# hydrop_board.net
KiCad netlist of a schematic drawn in EAGLE
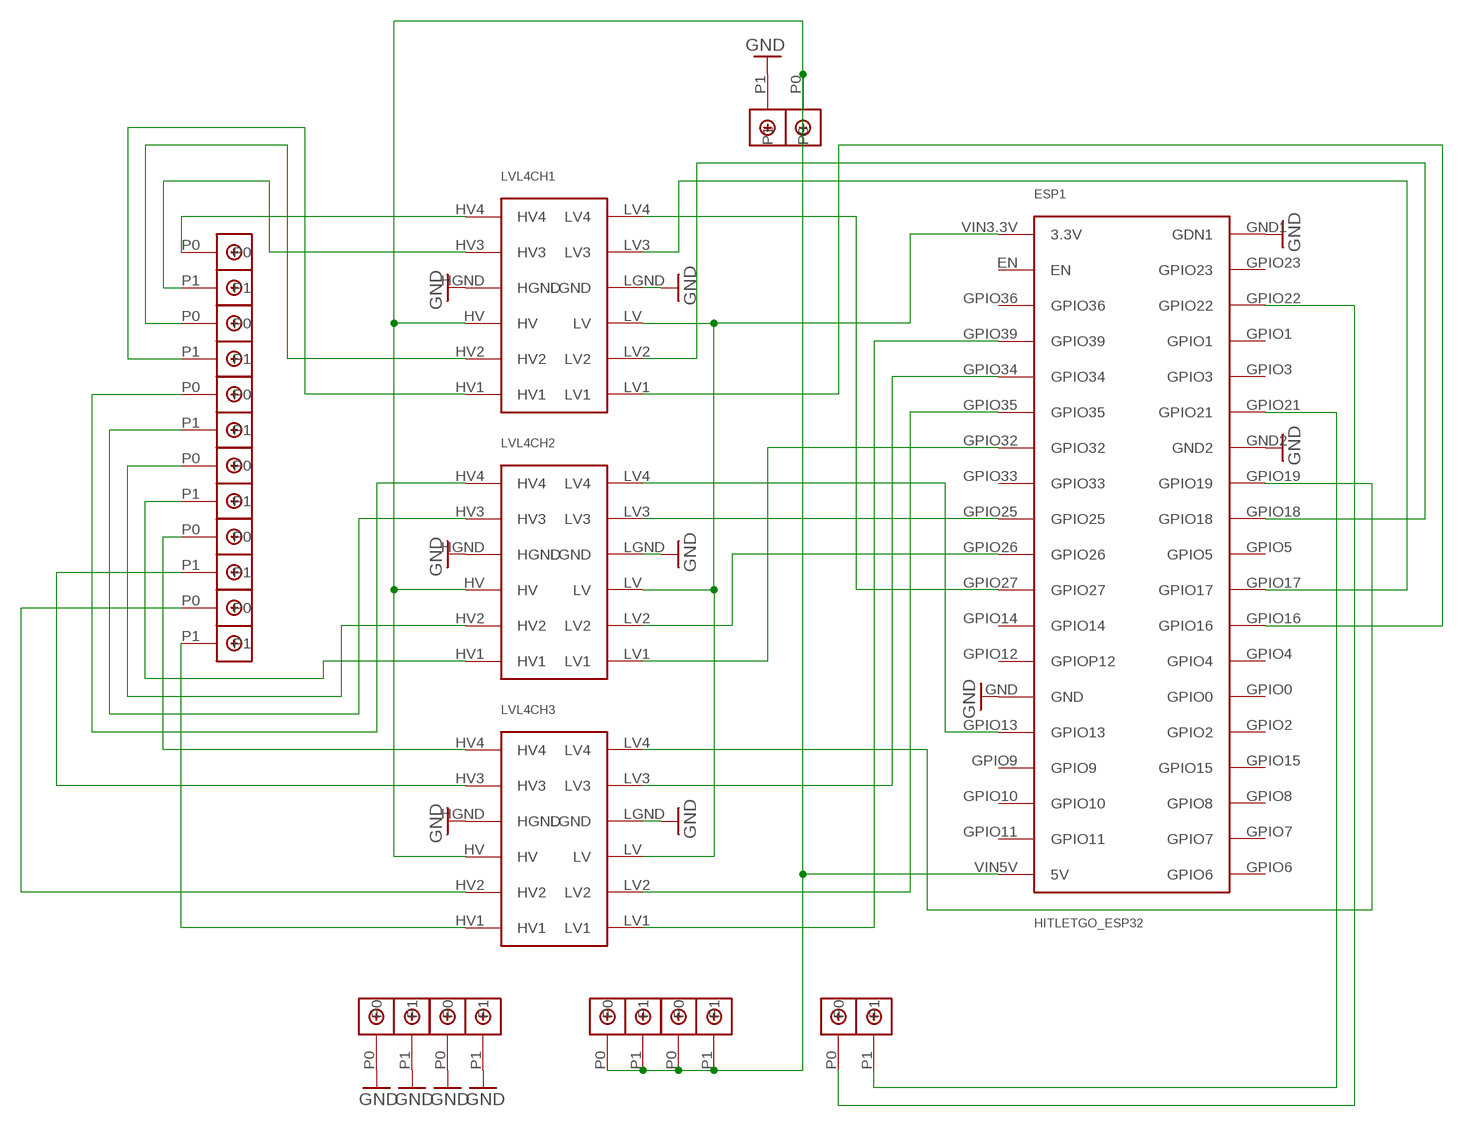
[diagram p0: schematic, sheet 1]

(export (version "E")
  (design (tool "Eeschema 10.0.6"))
  (components
    (comp (ref "ESP1")
      (value "HITLETGO_ESP32")
      (footprint "eagle-import:HILETGO_ESP32")
      (libsource (lib "eagle-import") (part "HITLETGO_ESP32"))
    )
    (comp (ref "LVL4CH1")
      (value "LEVELSHIFTER_4CH")
      (footprint "eagle-import:LEVELSHIFTER_4CH")
      (libsource (lib "eagle-import") (part "LEVELSHIFTER_4CH"))
    )
    (comp (ref "LVL4CH2")
      (value "LEVELSHIFTER_4CH")
      (footprint "eagle-import:LEVELSHIFTER_4CH")
      (libsource (lib "eagle-import") (part "LEVELSHIFTER_4CH"))
    )
    (comp (ref "LVL4CH3")
      (value "LEVELSHIFTER_4CH")
      (footprint "eagle-import:LEVELSHIFTER_4CH")
      (libsource (lib "eagle-import") (part "LEVELSHIFTER_4CH"))
    )
    (comp (ref "U$1")
      (value "DBCONN-1X2")
      (footprint "eagle-import:DBCONN-1X2")
      (libsource (lib "eagle-import") (part "DBCONN-1X2"))
    )
    (comp (ref "U$2")
      (value "DBCONN-1X2")
      (footprint "eagle-import:DBCONN-1X2")
      (libsource (lib "eagle-import") (part "DBCONN-1X2"))
    )
    (comp (ref "U$3")
      (value "DBCONN-1X2")
      (footprint "eagle-import:DBCONN-1X2")
      (libsource (lib "eagle-import") (part "DBCONN-1X2"))
    )
    (comp (ref "U$4")
      (value "DBCONN-1X2")
      (footprint "eagle-import:DBCONN-1X2")
      (libsource (lib "eagle-import") (part "DBCONN-1X2"))
    )
    (comp (ref "U$5")
      (value "DBCONN-1X2")
      (footprint "eagle-import:DBCONN-1X2")
      (libsource (lib "eagle-import") (part "DBCONN-1X2"))
    )
    (comp (ref "U$6")
      (value "DBCONN-1X2")
      (footprint "eagle-import:DBCONN-1X2")
      (libsource (lib "eagle-import") (part "DBCONN-1X2"))
    )
    (comp (ref "U$7")
      (value "DBCONN-1X2")
      (footprint "eagle-import:DBCONN-1X2")
      (libsource (lib "eagle-import") (part "DBCONN-1X2"))
    )
    (comp (ref "U$8")
      (value "DBCONN-1X2")
      (footprint "eagle-import:DBCONN-1X2")
      (libsource (lib "eagle-import") (part "DBCONN-1X2"))
    )
    (comp (ref "U$9")
      (value "DBCONN-1X2")
      (footprint "eagle-import:DBCONN-1X2")
      (libsource (lib "eagle-import") (part "DBCONN-1X2"))
    )
    (comp (ref "U$10")
      (value "DBCONN-1X2")
      (footprint "eagle-import:DBCONN-1X2")
      (libsource (lib "eagle-import") (part "DBCONN-1X2"))
    )
    (comp (ref "U$11")
      (value "DBCONN-1X2")
      (footprint "eagle-import:DBCONN-1X2")
      (libsource (lib "eagle-import") (part "DBCONN-1X2"))
    )
    (comp (ref "U$12")
      (value "DBCONN-1X2")
      (footprint "eagle-import:DBCONN-1X2")
      (libsource (lib "eagle-import") (part "DBCONN-1X2"))
    )
  )
  (nets
    (net (code "1") (name "GND") (class "Default")
      (node (ref "ESP1") (pin "GND") (pinfunction "GND_GND") (pintype "bidirectional"))
      (node (ref "ESP1") (pin "GND1") (pinfunction "GDN1_GND1") (pintype "bidirectional"))
      (node (ref "ESP1") (pin "GND2") (pinfunction "GND2_GND2") (pintype "bidirectional"))
      (node (ref "LVL4CH1") (pin "HGND") (pinfunction "HGND_HGND") (pintype "bidirectional"))
      (node (ref "LVL4CH1") (pin "LGND") (pinfunction "LGND_LGND") (pintype "bidirectional"))
      (node (ref "LVL4CH2") (pin "HGND") (pinfunction "HGND_HGND") (pintype "bidirectional"))
      (node (ref "LVL4CH2") (pin "LGND") (pinfunction "LGND_LGND") (pintype "bidirectional"))
      (node (ref "LVL4CH3") (pin "HGND") (pinfunction "HGND_HGND") (pintype "bidirectional"))
      (node (ref "LVL4CH3") (pin "LGND") (pinfunction "LGND_LGND") (pintype "bidirectional"))
      (node (ref "U$7") (pin "P1") (pinfunction "P1_P1") (pintype "bidirectional"))
      (node (ref "U$8") (pin "P0") (pinfunction "P0_P0") (pintype "bidirectional"))
      (node (ref "U$8") (pin "P1") (pinfunction "P1_P1") (pintype "bidirectional"))
      (node (ref "U$9") (pin "P0") (pinfunction "P0_P0") (pintype "bidirectional"))
      (node (ref "U$9") (pin "P1") (pinfunction "P1_P1") (pintype "bidirectional"))
    )
    (net (code "2") (name "Net-(ESP1-3.3V)") (class "Default")
      (node (ref "ESP1") (pin "VIN3.3V") (pinfunction "3.3V_VIN3.3V") (pintype "bidirectional"))
      (node (ref "LVL4CH1") (pin "LV") (pinfunction "LV_LV") (pintype "bidirectional"))
      (node (ref "LVL4CH2") (pin "LV") (pinfunction "LV_LV") (pintype "bidirectional"))
      (node (ref "LVL4CH3") (pin "LV") (pinfunction "LV_LV") (pintype "bidirectional"))
    )
    (net (code "3") (name "Net-(ESP1-5V)") (class "Default")
      (node (ref "ESP1") (pin "VIN5V") (pinfunction "5V_VIN5V") (pintype "bidirectional"))
      (node (ref "LVL4CH1") (pin "HV") (pinfunction "HV_HV") (pintype "bidirectional"))
      (node (ref "LVL4CH2") (pin "HV") (pinfunction "HV_HV") (pintype "bidirectional"))
      (node (ref "LVL4CH3") (pin "HV") (pinfunction "HV_HV") (pintype "bidirectional"))
      (node (ref "U$10") (pin "P0") (pinfunction "P0_P0") (pintype "bidirectional"))
      (node (ref "U$10") (pin "P1") (pinfunction "P1_P1") (pintype "bidirectional"))
      (node (ref "U$11") (pin "P0") (pinfunction "P0_P0") (pintype "bidirectional"))
      (node (ref "U$11") (pin "P1") (pinfunction "P1_P1") (pintype "bidirectional"))
      (node (ref "U$7") (pin "P0") (pinfunction "P0_P0") (pintype "bidirectional"))
    )
    (net (code "4") (name "Net-(ESP1-PadGPIO13)") (class "Default")
      (node (ref "ESP1") (pin "GPIO13") (pinfunction "GPIO13_GPIO13") (pintype "bidirectional"))
      (node (ref "LVL4CH2") (pin "LV4") (pinfunction "LV4_LV4") (pintype "bidirectional"))
    )
    (net (code "5") (name "Net-(ESP1-PadGPIO16)") (class "Default")
      (node (ref "ESP1") (pin "GPIO16") (pinfunction "GPIO16_GPIO16") (pintype "bidirectional"))
      (node (ref "LVL4CH1") (pin "LV1") (pinfunction "LV1_LV1") (pintype "bidirectional"))
    )
    (net (code "6") (name "Net-(ESP1-PadGPIO17)") (class "Default")
      (node (ref "ESP1") (pin "GPIO17") (pinfunction "GPIO17_GPIO17") (pintype "bidirectional"))
      (node (ref "LVL4CH1") (pin "LV3") (pinfunction "LV3_LV3") (pintype "bidirectional"))
    )
    (net (code "7") (name "Net-(ESP1-PadGPIO18)") (class "Default")
      (node (ref "ESP1") (pin "GPIO18") (pinfunction "GPIO18_GPIO18") (pintype "bidirectional"))
      (node (ref "LVL4CH1") (pin "LV2") (pinfunction "LV2_LV2") (pintype "bidirectional"))
    )
    (net (code "8") (name "Net-(ESP1-PadGPIO19)") (class "Default")
      (node (ref "ESP1") (pin "GPIO19") (pinfunction "GPIO19_GPIO19") (pintype "bidirectional"))
      (node (ref "LVL4CH3") (pin "LV4") (pinfunction "LV4_LV4") (pintype "bidirectional"))
    )
    (net (code "9") (name "Net-(ESP1-PadGPIO21)") (class "Default")
      (node (ref "ESP1") (pin "GPIO21") (pinfunction "GPIO21_GPIO21") (pintype "bidirectional"))
      (node (ref "U$12") (pin "P1") (pinfunction "P1_P1") (pintype "bidirectional"))
    )
    (net (code "10") (name "Net-(ESP1-PadGPIO22)") (class "Default")
      (node (ref "ESP1") (pin "GPIO22") (pinfunction "GPIO22_GPIO22") (pintype "bidirectional"))
      (node (ref "U$12") (pin "P0") (pinfunction "P0_P0") (pintype "bidirectional"))
    )
    (net (code "11") (name "Net-(ESP1-PadGPIO25)") (class "Default")
      (node (ref "ESP1") (pin "GPIO25") (pinfunction "GPIO25_GPIO25") (pintype "bidirectional"))
      (node (ref "LVL4CH2") (pin "LV3") (pinfunction "LV3_LV3") (pintype "bidirectional"))
    )
    (net (code "12") (name "Net-(ESP1-PadGPIO26)") (class "Default")
      (node (ref "ESP1") (pin "GPIO26") (pinfunction "GPIO26_GPIO26") (pintype "bidirectional"))
      (node (ref "LVL4CH2") (pin "LV2") (pinfunction "LV2_LV2") (pintype "bidirectional"))
    )
    (net (code "13") (name "Net-(ESP1-PadGPIO27)") (class "Default")
      (node (ref "ESP1") (pin "GPIO27") (pinfunction "GPIO27_GPIO27") (pintype "bidirectional"))
      (node (ref "LVL4CH1") (pin "LV4") (pinfunction "LV4_LV4") (pintype "bidirectional"))
    )
    (net (code "14") (name "Net-(ESP1-PadGPIO32)") (class "Default")
      (node (ref "ESP1") (pin "GPIO32") (pinfunction "GPIO32_GPIO32") (pintype "bidirectional"))
      (node (ref "LVL4CH2") (pin "LV1") (pinfunction "LV1_LV1") (pintype "bidirectional"))
    )
    (net (code "15") (name "Net-(ESP1-PadGPIO34)") (class "Default")
      (node (ref "ESP1") (pin "GPIO34") (pinfunction "GPIO34_GPIO34") (pintype "bidirectional"))
      (node (ref "LVL4CH3") (pin "LV3") (pinfunction "LV3_LV3") (pintype "bidirectional"))
    )
    (net (code "16") (name "Net-(ESP1-PadGPIO35)") (class "Default")
      (node (ref "ESP1") (pin "GPIO35") (pinfunction "GPIO35_GPIO35") (pintype "bidirectional"))
      (node (ref "LVL4CH3") (pin "LV2") (pinfunction "LV2_LV2") (pintype "bidirectional"))
    )
    (net (code "17") (name "Net-(ESP1-PadGPIO39)") (class "Default")
      (node (ref "ESP1") (pin "GPIO39") (pinfunction "GPIO39_GPIO39") (pintype "bidirectional"))
      (node (ref "LVL4CH3") (pin "LV1") (pinfunction "LV1_LV1") (pintype "bidirectional"))
    )
    (net (code "18") (name "Net-(LVL4CH1-PadHV1)") (class "Default")
      (node (ref "LVL4CH1") (pin "HV1") (pinfunction "HV1_HV1") (pintype "bidirectional"))
      (node (ref "U$2") (pin "P1") (pinfunction "P1_P1") (pintype "bidirectional"))
    )
    (net (code "19") (name "Net-(LVL4CH1-PadHV2)") (class "Default")
      (node (ref "LVL4CH1") (pin "HV2") (pinfunction "HV2_HV2") (pintype "bidirectional"))
      (node (ref "U$2") (pin "P0") (pinfunction "P0_P0") (pintype "bidirectional"))
    )
    (net (code "20") (name "Net-(LVL4CH1-PadHV3)") (class "Default")
      (node (ref "LVL4CH1") (pin "HV3") (pinfunction "HV3_HV3") (pintype "bidirectional"))
      (node (ref "U$1") (pin "P1") (pinfunction "P1_P1") (pintype "bidirectional"))
    )
    (net (code "21") (name "Net-(LVL4CH1-PadHV4)") (class "Default")
      (node (ref "LVL4CH1") (pin "HV4") (pinfunction "HV4_HV4") (pintype "bidirectional"))
      (node (ref "U$1") (pin "P0") (pinfunction "P0_P0") (pintype "bidirectional"))
    )
    (net (code "22") (name "Net-(LVL4CH2-PadHV1)") (class "Default")
      (node (ref "LVL4CH2") (pin "HV1") (pinfunction "HV1_HV1") (pintype "bidirectional"))
      (node (ref "U$4") (pin "P1") (pinfunction "P1_P1") (pintype "bidirectional"))
    )
    (net (code "23") (name "Net-(LVL4CH2-PadHV2)") (class "Default")
      (node (ref "LVL4CH2") (pin "HV2") (pinfunction "HV2_HV2") (pintype "bidirectional"))
      (node (ref "U$4") (pin "P0") (pinfunction "P0_P0") (pintype "bidirectional"))
    )
    (net (code "24") (name "Net-(LVL4CH2-PadHV3)") (class "Default")
      (node (ref "LVL4CH2") (pin "HV3") (pinfunction "HV3_HV3") (pintype "bidirectional"))
      (node (ref "U$3") (pin "P1") (pinfunction "P1_P1") (pintype "bidirectional"))
    )
    (net (code "25") (name "Net-(LVL4CH2-PadHV4)") (class "Default")
      (node (ref "LVL4CH2") (pin "HV4") (pinfunction "HV4_HV4") (pintype "bidirectional"))
      (node (ref "U$3") (pin "P0") (pinfunction "P0_P0") (pintype "bidirectional"))
    )
    (net (code "26") (name "Net-(LVL4CH3-PadHV1)") (class "Default")
      (node (ref "LVL4CH3") (pin "HV1") (pinfunction "HV1_HV1") (pintype "bidirectional"))
      (node (ref "U$6") (pin "P1") (pinfunction "P1_P1") (pintype "bidirectional"))
    )
    (net (code "27") (name "Net-(LVL4CH3-PadHV2)") (class "Default")
      (node (ref "LVL4CH3") (pin "HV2") (pinfunction "HV2_HV2") (pintype "bidirectional"))
      (node (ref "U$6") (pin "P0") (pinfunction "P0_P0") (pintype "bidirectional"))
    )
    (net (code "28") (name "Net-(LVL4CH3-PadHV3)") (class "Default")
      (node (ref "LVL4CH3") (pin "HV3") (pinfunction "HV3_HV3") (pintype "bidirectional"))
      (node (ref "U$5") (pin "P1") (pinfunction "P1_P1") (pintype "bidirectional"))
    )
    (net (code "29") (name "Net-(LVL4CH3-PadHV4)") (class "Default")
      (node (ref "LVL4CH3") (pin "HV4") (pinfunction "HV4_HV4") (pintype "bidirectional"))
      (node (ref "U$5") (pin "P0") (pinfunction "P0_P0") (pintype "bidirectional"))
    )
    (net (code "30") (name "unconnected-(ESP1-GPIOP12-PadGPIO12)") (class "Default")
      (node (ref "ESP1") (pin "GPIO12") (pinfunction "GPIOP12_GPIO12") (pintype "bidirectional"))
    )
    (net (code "31") (name "unconnected-(ESP1-PadEN)") (class "Default")
      (node (ref "ESP1") (pin "EN") (pinfunction "EN_EN") (pintype "bidirectional"))
    )
    (net (code "32") (name "unconnected-(ESP1-PadGPIO0)") (class "Default")
      (node (ref "ESP1") (pin "GPIO0") (pinfunction "GPIO0_GPIO0") (pintype "bidirectional"))
    )
    (net (code "33") (name "unconnected-(ESP1-PadGPIO1)") (class "Default")
      (node (ref "ESP1") (pin "GPIO1") (pinfunction "GPIO1_GPIO1") (pintype "bidirectional"))
    )
    (net (code "34") (name "unconnected-(ESP1-PadGPIO2)") (class "Default")
      (node (ref "ESP1") (pin "GPIO2") (pinfunction "GPIO2_GPIO2") (pintype "bidirectional"))
    )
    (net (code "35") (name "unconnected-(ESP1-PadGPIO3)") (class "Default")
      (node (ref "ESP1") (pin "GPIO3") (pinfunction "GPIO3_GPIO3") (pintype "bidirectional"))
    )
    (net (code "36") (name "unconnected-(ESP1-PadGPIO4)") (class "Default")
      (node (ref "ESP1") (pin "GPIO4") (pinfunction "GPIO4_GPIO4") (pintype "bidirectional"))
    )
    (net (code "37") (name "unconnected-(ESP1-PadGPIO5)") (class "Default")
      (node (ref "ESP1") (pin "GPIO5") (pinfunction "GPIO5_GPIO5") (pintype "bidirectional"))
    )
    (net (code "38") (name "unconnected-(ESP1-PadGPIO6)") (class "Default")
      (node (ref "ESP1") (pin "GPIO6") (pinfunction "GPIO6_GPIO6") (pintype "bidirectional"))
    )
    (net (code "39") (name "unconnected-(ESP1-PadGPIO7)") (class "Default")
      (node (ref "ESP1") (pin "GPIO7") (pinfunction "GPIO7_GPIO7") (pintype "bidirectional"))
    )
    (net (code "40") (name "unconnected-(ESP1-PadGPIO8)") (class "Default")
      (node (ref "ESP1") (pin "GPIO8") (pinfunction "GPIO8_GPIO8") (pintype "bidirectional"))
    )
    (net (code "41") (name "unconnected-(ESP1-PadGPIO9)") (class "Default")
      (node (ref "ESP1") (pin "GPIO9") (pinfunction "GPIO9_GPIO9") (pintype "bidirectional"))
    )
    (net (code "42") (name "unconnected-(ESP1-PadGPIO10)") (class "Default")
      (node (ref "ESP1") (pin "GPIO10") (pinfunction "GPIO10_GPIO10") (pintype "bidirectional"))
    )
    (net (code "43") (name "unconnected-(ESP1-PadGPIO11)") (class "Default")
      (node (ref "ESP1") (pin "GPIO11") (pinfunction "GPIO11_GPIO11") (pintype "bidirectional"))
    )
    (net (code "44") (name "unconnected-(ESP1-PadGPIO14)") (class "Default")
      (node (ref "ESP1") (pin "GPIO14") (pinfunction "GPIO14_GPIO14") (pintype "bidirectional"))
    )
    (net (code "45") (name "unconnected-(ESP1-PadGPIO15)") (class "Default")
      (node (ref "ESP1") (pin "GPIO15") (pinfunction "GPIO15_GPIO15") (pintype "bidirectional"))
    )
    (net (code "46") (name "unconnected-(ESP1-PadGPIO23)") (class "Default")
      (node (ref "ESP1") (pin "GPIO23") (pinfunction "GPIO23_GPIO23") (pintype "bidirectional"))
    )
    (net (code "47") (name "unconnected-(ESP1-PadGPIO33)") (class "Default")
      (node (ref "ESP1") (pin "GPIO33") (pinfunction "GPIO33_GPIO33") (pintype "bidirectional"))
    )
    (net (code "48") (name "unconnected-(ESP1-PadGPIO36)") (class "Default")
      (node (ref "ESP1") (pin "GPIO36") (pinfunction "GPIO36_GPIO36") (pintype "bidirectional"))
    )
  )
)
